# whare_hauora_sensor_r1_2.net
KiCad netlist of a schematic drawn in EAGLE
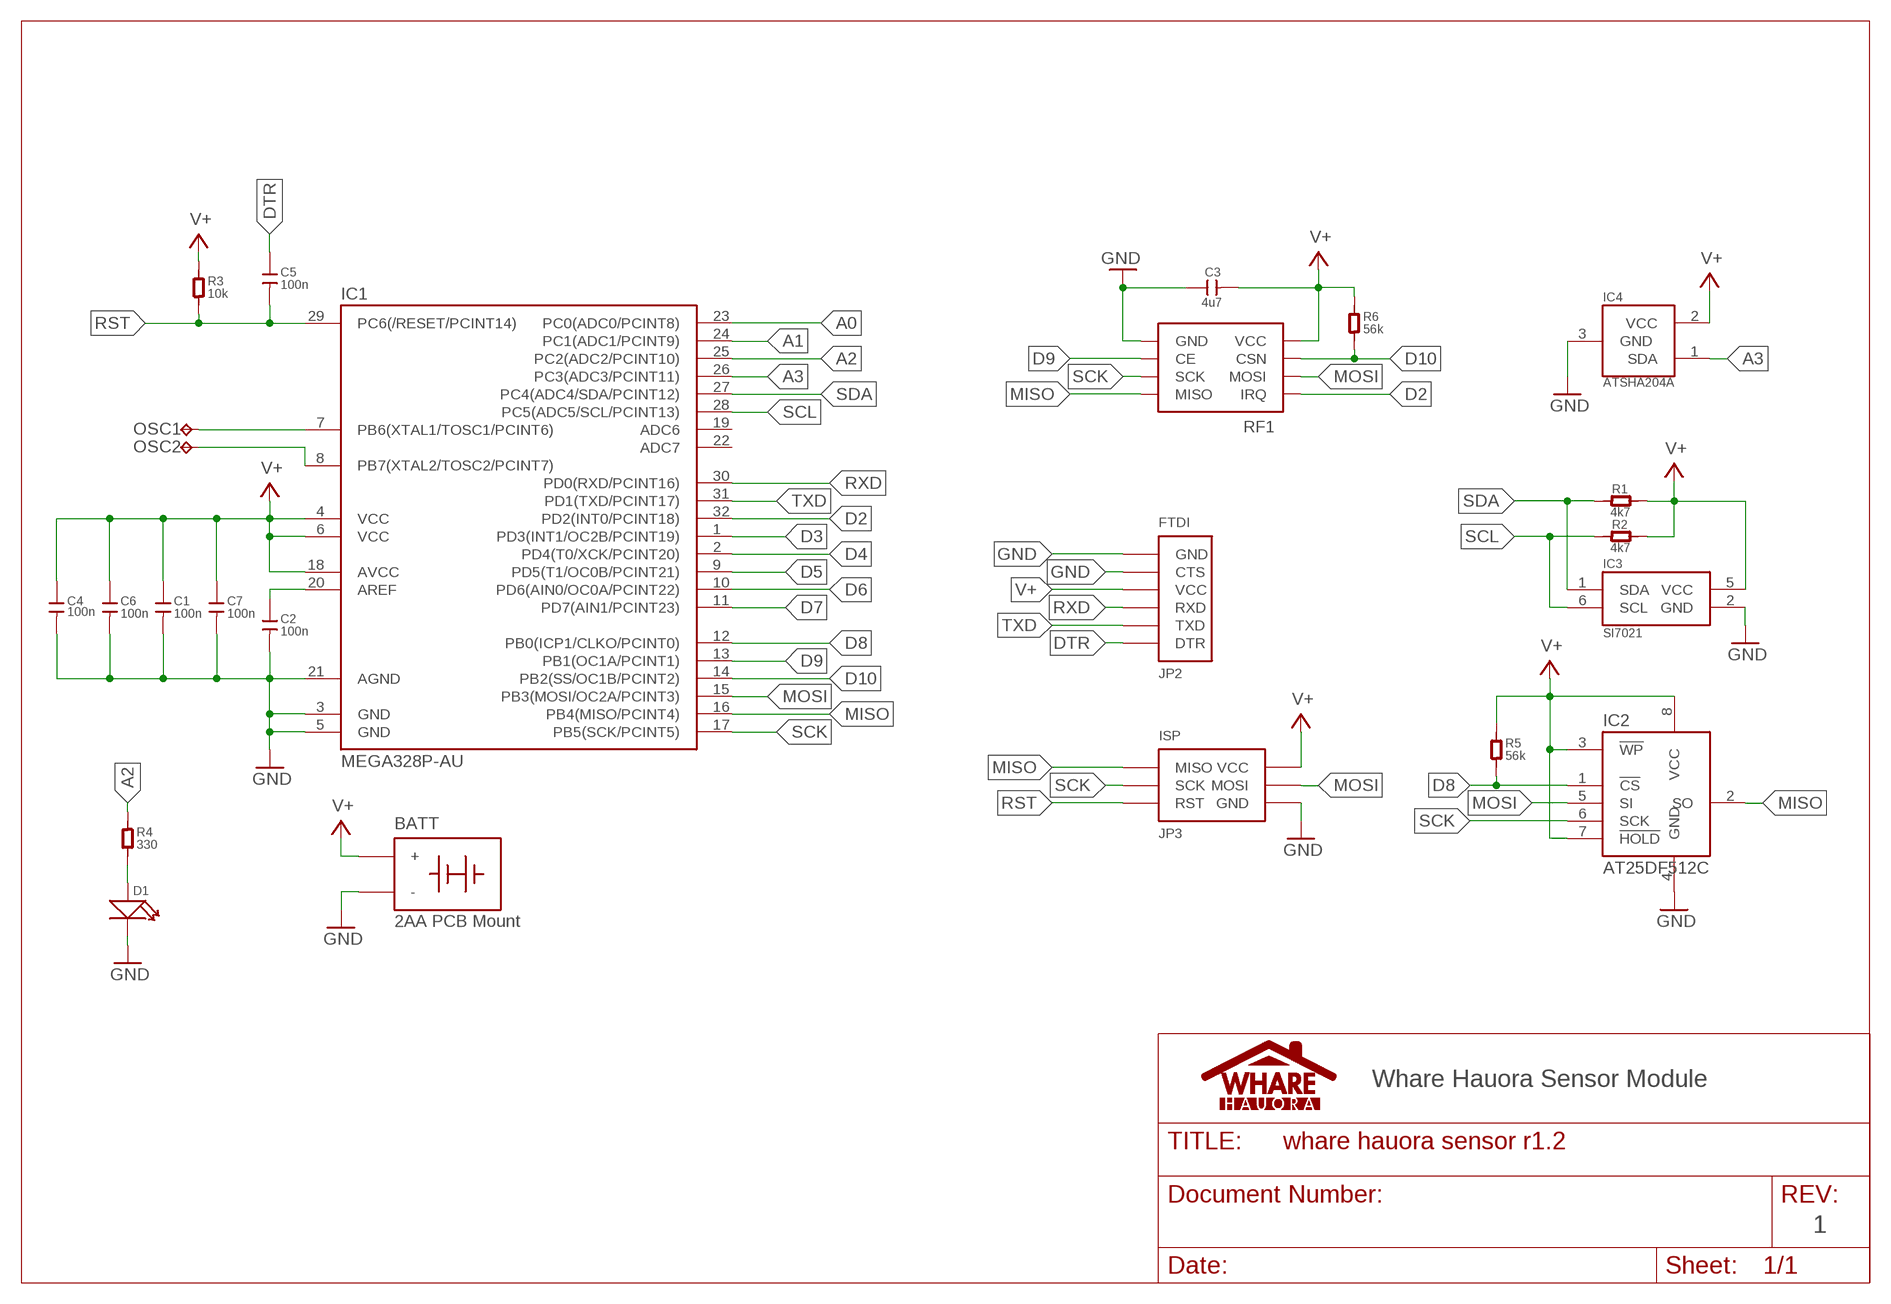
[diagram p0: schematic, sheet 1]

(export (version "E")
  (design (tool "Eeschema 10.0.6"))
  (components
    (comp (ref "BATT")
      (value "2AA-PACK")
      (footprint "eagle-import:2AA-PACK_")
      (libsource (lib "eagle-import") (part "2AA-PACK"))
    )
    (comp (ref "C1")
      (value "100n")
      (footprint "eagle-import:C0603")
      (libsource (lib "eagle-import") (part "CAP-0603"))
    )
    (comp (ref "C2")
      (value "100n")
      (footprint "eagle-import:C0603")
      (libsource (lib "eagle-import") (part "CAP-0603"))
    )
    (comp (ref "C3")
      (value "4u7")
      (footprint "eagle-import:C0603")
      (libsource (lib "eagle-import") (part "CAP-0603"))
    )
    (comp (ref "C4")
      (value "100n")
      (footprint "eagle-import:C0603")
      (libsource (lib "eagle-import") (part "CAP-0603"))
    )
    (comp (ref "C5")
      (value "100n")
      (footprint "eagle-import:C0603")
      (libsource (lib "eagle-import") (part "CAP-0603"))
    )
    (comp (ref "C6")
      (value "100n")
      (footprint "eagle-import:C0603")
      (libsource (lib "eagle-import") (part "CAP-0603"))
    )
    (comp (ref "C7")
      (value "100n")
      (footprint "eagle-import:C0603")
      (libsource (lib "eagle-import") (part "CAP-0603"))
    )
    (comp (ref "D1")
      (value "LED-0603")
      (footprint "eagle-import:LED-0603")
      (libsource (lib "eagle-import") (part "LED-0603"))
    )
    (comp (ref "IC1")
      (value "MEGA328P-AU")
      (footprint "eagle-import:TQFP32-08")
      (libsource (lib "eagle-import") (part "MEGA48/88/168-AU"))
    )
    (comp (ref "IC2")
      (value "AT25DF512C")
      (footprint "eagle-import:SO8")
      (libsource (lib "eagle-import") (part "AT25DF512C"))
    )
    (comp (ref "IC3")
      (value "SI7021")
      (footprint "eagle-import:DFN6")
      (libsource (lib "eagle-import") (part "SI7021"))
    )
    (comp (ref "IC4")
      (value "ATSHA204A")
      (footprint "eagle-import:SOT23")
      (libsource (lib "eagle-import") (part "ATSHA204A"))
    )
    (comp (ref "JP2")
      (value "FTDI")
      (footprint "eagle-import:FTDI")
      (libsource (lib "eagle-import") (part "FTDI"))
    )
    (comp (ref "JP3")
      (value "ISP")
      (footprint "eagle-import:ISP")
      (libsource (lib "eagle-import") (part "ISP"))
    )
    (comp (ref "OSC1")
      (value "TPTP10R")
      (footprint "eagle-import:TP10R")
      (libsource (lib "eagle-import") (part "TPTP10R"))
    )
    (comp (ref "OSC2")
      (value "TPTP10R")
      (footprint "eagle-import:TP10R")
      (libsource (lib "eagle-import") (part "TPTP10R"))
    )
    (comp (ref "R1")
      (value "4k7")
      (footprint "eagle-import:R0603")
      (libsource (lib "eagle-import") (part "R-0603"))
    )
    (comp (ref "R2")
      (value "4k7")
      (footprint "eagle-import:R0603")
      (libsource (lib "eagle-import") (part "R-0603"))
    )
    (comp (ref "R3")
      (value "10k")
      (footprint "eagle-import:R0603")
      (libsource (lib "eagle-import") (part "R-0603"))
    )
    (comp (ref "R4")
      (value "330")
      (footprint "eagle-import:R0603")
      (libsource (lib "eagle-import") (part "R-0603"))
    )
    (comp (ref "R5")
      (value "56k")
      (footprint "eagle-import:R0603")
      (libsource (lib "eagle-import") (part "R-0603"))
    )
    (comp (ref "R6")
      (value "56k")
      (footprint "eagle-import:R0603")
      (libsource (lib "eagle-import") (part "R-0603"))
    )
    (comp (ref "RF1")
      (value "NRF24L01+")
      (footprint "eagle-import:NRF24L01+")
      (libsource (lib "eagle-import") (part "NRF24L01+"))
    )
  )
  (nets
    (net (code "1") (name "A0") (class "Default")
      (node (ref "IC1") (pin "23") (pinfunction "PC0(ADC0/PCINT8)_23") (pintype "bidirectional"))
    )
    (net (code "2") (name "A1") (class "Default")
      (node (ref "IC1") (pin "24") (pinfunction "PC1(ADC1/PCINT9)_24") (pintype "bidirectional"))
    )
    (net (code "3") (name "A2") (class "Default")
      (node (ref "IC1") (pin "25") (pinfunction "PC2(ADC2/PCINT10)_25") (pintype "bidirectional"))
      (node (ref "R4") (pin "1") (pinfunction "1_1") (pintype "bidirectional"))
    )
    (net (code "4") (name "A3") (class "Default")
      (node (ref "IC1") (pin "26") (pinfunction "PC3(ADC3/PCINT11)_26") (pintype "bidirectional"))
      (node (ref "IC4") (pin "1") (pinfunction "SDA_1") (pintype "bidirectional"))
    )
    (net (code "5") (name "D2") (class "Default")
      (node (ref "IC1") (pin "32") (pinfunction "PD2(INT0/PCINT18)_32") (pintype "bidirectional"))
      (node (ref "RF1") (pin "P$8") (pinfunction "IRQ_P$8") (pintype "bidirectional"))
    )
    (net (code "6") (name "D3") (class "Default")
      (node (ref "IC1") (pin "1") (pinfunction "PD3(INT1/OC2B/PCINT19)_1") (pintype "bidirectional"))
    )
    (net (code "7") (name "D4") (class "Default")
      (node (ref "IC1") (pin "2") (pinfunction "PD4(T0/XCK/PCINT20)_2") (pintype "bidirectional"))
    )
    (net (code "8") (name "D5") (class "Default")
      (node (ref "IC1") (pin "9") (pinfunction "PD5(T1/OC0B/PCINT21)_9") (pintype "bidirectional"))
    )
    (net (code "9") (name "D6") (class "Default")
      (node (ref "IC1") (pin "10") (pinfunction "PD6(AIN0/OC0A/PCINT22)_10") (pintype "bidirectional"))
    )
    (net (code "10") (name "D7") (class "Default")
      (node (ref "IC1") (pin "11") (pinfunction "PD7(AIN1/PCINT23)_11") (pintype "bidirectional"))
    )
    (net (code "11") (name "D8") (class "Default")
      (node (ref "IC1") (pin "12") (pinfunction "PB0(ICP1/CLKO/PCINT0)_12") (pintype "bidirectional"))
      (node (ref "IC2") (pin "1") (pinfunction "~{CS}_1") (pintype "input"))
      (node (ref "R5") (pin "1") (pinfunction "1_1") (pintype "bidirectional"))
    )
    (net (code "12") (name "D9") (class "Default")
      (node (ref "IC1") (pin "13") (pinfunction "PB1(OC1A/PCINT1)_13") (pintype "bidirectional"))
      (node (ref "RF1") (pin "P$3") (pinfunction "CE_P$3") (pintype "bidirectional"))
    )
    (net (code "13") (name "D10") (class "Default")
      (node (ref "IC1") (pin "14") (pinfunction "PB2(SS/OC1B/PCINT2)_14") (pintype "bidirectional"))
      (node (ref "R6") (pin "1") (pinfunction "1_1") (pintype "bidirectional"))
      (node (ref "RF1") (pin "P$4") (pinfunction "CSN_P$4") (pintype "bidirectional"))
    )
    (net (code "14") (name "DTR") (class "Default")
      (node (ref "C5") (pin "1") (pinfunction "1_1") (pintype "passive"))
      (node (ref "JP2") (pin "DTR") (pinfunction "DTR_DTR") (pintype "bidirectional"))
    )
    (net (code "15") (name "GND") (class "Default")
      (node (ref "BATT") (pin "-") (pinfunction "-_-") (pintype "bidirectional"))
      (node (ref "C1") (pin "2") (pinfunction "2_2") (pintype "passive"))
      (node (ref "C2") (pin "2") (pinfunction "2_2") (pintype "passive"))
      (node (ref "C3") (pin "1") (pinfunction "1_1") (pintype "passive"))
      (node (ref "C4") (pin "2") (pinfunction "2_2") (pintype "passive"))
      (node (ref "C6") (pin "2") (pinfunction "2_2") (pintype "passive"))
      (node (ref "C7") (pin "2") (pinfunction "2_2") (pintype "passive"))
      (node (ref "D1") (pin "-") (pinfunction "-_-") (pintype "passive"))
      (node (ref "IC1") (pin "21") (pinfunction "AGND_21") (pintype "power_in"))
      (node (ref "IC1") (pin "3") (pinfunction "GND_3") (pintype "power_in"))
      (node (ref "IC1") (pin "5") (pinfunction "GND_5") (pintype "power_in"))
      (node (ref "IC2") (pin "4") (pinfunction "GND_4") (pintype "power_in"))
      (node (ref "IC3") (pin "2") (pinfunction "GND_2") (pintype "bidirectional"))
      (node (ref "IC4") (pin "3") (pinfunction "GND_3") (pintype "bidirectional"))
      (node (ref "JP2") (pin "CTS") (pinfunction "CTS_CTS") (pintype "bidirectional"))
      (node (ref "JP2") (pin "GND") (pinfunction "GND_GND") (pintype "bidirectional"))
      (node (ref "JP3") (pin "GND") (pinfunction "GND_GND") (pintype "bidirectional"))
      (node (ref "RF1") (pin "P$1") (pinfunction "GND_P$1") (pintype "bidirectional"))
    )
    (net (code "16") (name "MISO") (class "Default")
      (node (ref "IC1") (pin "16") (pinfunction "PB4(MISO/PCINT4)_16") (pintype "bidirectional"))
      (node (ref "IC2") (pin "2") (pinfunction "SO_2") (pintype "output"))
      (node (ref "JP3") (pin "MISO") (pinfunction "MISO_MISO") (pintype "bidirectional"))
      (node (ref "RF1") (pin "P$7") (pinfunction "MISO_P$7") (pintype "bidirectional"))
    )
    (net (code "17") (name "MOSI") (class "Default")
      (node (ref "IC1") (pin "15") (pinfunction "PB3(MOSI/OC2A/PCINT3)_15") (pintype "bidirectional"))
      (node (ref "IC2") (pin "5") (pinfunction "SI_5") (pintype "input"))
      (node (ref "JP3") (pin "MOSI") (pinfunction "MOSI_MOSI") (pintype "bidirectional"))
      (node (ref "RF1") (pin "P$6") (pinfunction "MOSI_P$6") (pintype "bidirectional"))
    )
    (net (code "18") (name "Net-(D1-Pad+)") (class "Default")
      (node (ref "D1") (pin "+") (pinfunction "+_+") (pintype "passive"))
      (node (ref "R4") (pin "2") (pinfunction "2_2") (pintype "bidirectional"))
    )
    (net (code "19") (name "Net-(IC1-AREF)") (class "Default")
      (node (ref "C2") (pin "1") (pinfunction "1_1") (pintype "passive"))
      (node (ref "IC1") (pin "20") (pinfunction "AREF_20") (pintype "passive"))
    )
    (net (code "20") (name "Net-(IC1-PB6(XTAL1{slash}TOSC1{slash}PCINT6))") (class "Default")
      (node (ref "IC1") (pin "7") (pinfunction "PB6(XTAL1/TOSC1/PCINT6)_7") (pintype "bidirectional"))
      (node (ref "OSC1") (pin "TP") (pinfunction "TP_TP") (pintype "input"))
    )
    (net (code "21") (name "Net-(IC1-PB7(XTAL2{slash}TOSC2{slash}PCINT7))") (class "Default")
      (node (ref "IC1") (pin "8") (pinfunction "PB7(XTAL2/TOSC2/PCINT7)_8") (pintype "bidirectional"))
      (node (ref "OSC2") (pin "TP") (pinfunction "TP_TP") (pintype "input"))
    )
    (net (code "22") (name "RST") (class "Default")
      (node (ref "C5") (pin "2") (pinfunction "2_2") (pintype "passive"))
      (node (ref "IC1") (pin "29") (pinfunction "PC6(/RESET/PCINT14)_29") (pintype "bidirectional"))
      (node (ref "JP3") (pin "RST") (pinfunction "RST_RST") (pintype "bidirectional"))
      (node (ref "R3") (pin "1") (pinfunction "1_1") (pintype "bidirectional"))
    )
    (net (code "23") (name "RXD") (class "Default")
      (node (ref "IC1") (pin "30") (pinfunction "PD0(RXD/PCINT16)_30") (pintype "bidirectional"))
      (node (ref "JP2") (pin "RXD") (pinfunction "RXD_RXD") (pintype "bidirectional"))
    )
    (net (code "24") (name "SCK") (class "Default")
      (node (ref "IC1") (pin "17") (pinfunction "PB5(SCK/PCINT5)_17") (pintype "bidirectional"))
      (node (ref "IC2") (pin "6") (pinfunction "SCK_6") (pintype "input"))
      (node (ref "JP3") (pin "SCK") (pinfunction "SCK_SCK") (pintype "bidirectional"))
      (node (ref "RF1") (pin "P$5") (pinfunction "SCK_P$5") (pintype "bidirectional"))
    )
    (net (code "25") (name "SCL") (class "Default")
      (node (ref "IC1") (pin "28") (pinfunction "PC5(ADC5/SCL/PCINT13)_28") (pintype "bidirectional"))
      (node (ref "IC3") (pin "6") (pinfunction "SCL_6") (pintype "bidirectional"))
      (node (ref "R2") (pin "1") (pinfunction "1_1") (pintype "bidirectional"))
    )
    (net (code "26") (name "SDA") (class "Default")
      (node (ref "IC1") (pin "27") (pinfunction "PC4(ADC4/SDA/PCINT12)_27") (pintype "bidirectional"))
      (node (ref "IC3") (pin "1") (pinfunction "SDA_1") (pintype "bidirectional"))
      (node (ref "R1") (pin "1") (pinfunction "1_1") (pintype "bidirectional"))
    )
    (net (code "27") (name "TXD") (class "Default")
      (node (ref "IC1") (pin "31") (pinfunction "PD1(TXD/PCINT17)_31") (pintype "bidirectional"))
      (node (ref "JP2") (pin "TXD") (pinfunction "TXD_TXD") (pintype "bidirectional"))
    )
    (net (code "28") (name "V+") (class "Default")
      (node (ref "BATT") (pin "+") (pinfunction "+_+") (pintype "bidirectional"))
      (node (ref "C1") (pin "1") (pinfunction "1_1") (pintype "passive"))
      (node (ref "C3") (pin "2") (pinfunction "2_2") (pintype "passive"))
      (node (ref "C4") (pin "1") (pinfunction "1_1") (pintype "passive"))
      (node (ref "C6") (pin "1") (pinfunction "1_1") (pintype "passive"))
      (node (ref "C7") (pin "1") (pinfunction "1_1") (pintype "passive"))
      (node (ref "IC1") (pin "18") (pinfunction "AVCC_18") (pintype "passive"))
      (node (ref "IC1") (pin "4") (pinfunction "VCC_4") (pintype "power_in"))
      (node (ref "IC1") (pin "6") (pinfunction "VCC_6") (pintype "power_in"))
      (node (ref "IC2") (pin "3") (pinfunction "~{WP}_3") (pintype "input"))
      (node (ref "IC2") (pin "7") (pinfunction "~{HOLD}_7") (pintype "input"))
      (node (ref "IC2") (pin "8") (pinfunction "VCC_8") (pintype "bidirectional"))
      (node (ref "IC3") (pin "5") (pinfunction "VCC_5") (pintype "bidirectional"))
      (node (ref "IC4") (pin "2") (pinfunction "VCC_2") (pintype "bidirectional"))
      (node (ref "JP2") (pin "VCC") (pinfunction "VCC_VCC") (pintype "bidirectional"))
      (node (ref "JP3") (pin "VCC") (pinfunction "VCC_VCC") (pintype "bidirectional"))
      (node (ref "R1") (pin "2") (pinfunction "2_2") (pintype "bidirectional"))
      (node (ref "R2") (pin "2") (pinfunction "2_2") (pintype "bidirectional"))
      (node (ref "R3") (pin "2") (pinfunction "2_2") (pintype "bidirectional"))
      (node (ref "R5") (pin "2") (pinfunction "2_2") (pintype "bidirectional"))
      (node (ref "R6") (pin "2") (pinfunction "2_2") (pintype "bidirectional"))
      (node (ref "RF1") (pin "P$2") (pinfunction "VCC_P$2") (pintype "bidirectional"))
    )
    (net (code "29") (name "unconnected-(IC1-ADC6-Pad19)") (class "Default")
      (node (ref "IC1") (pin "19") (pinfunction "ADC6_19") (pintype "passive"))
    )
    (net (code "30") (name "unconnected-(IC1-ADC7-Pad22)") (class "Default")
      (node (ref "IC1") (pin "22") (pinfunction "ADC7_22") (pintype "passive"))
    )
  )
)
